# Keypad_Schematic.net
KiCad netlist of a schematic drawn in Altium Designer
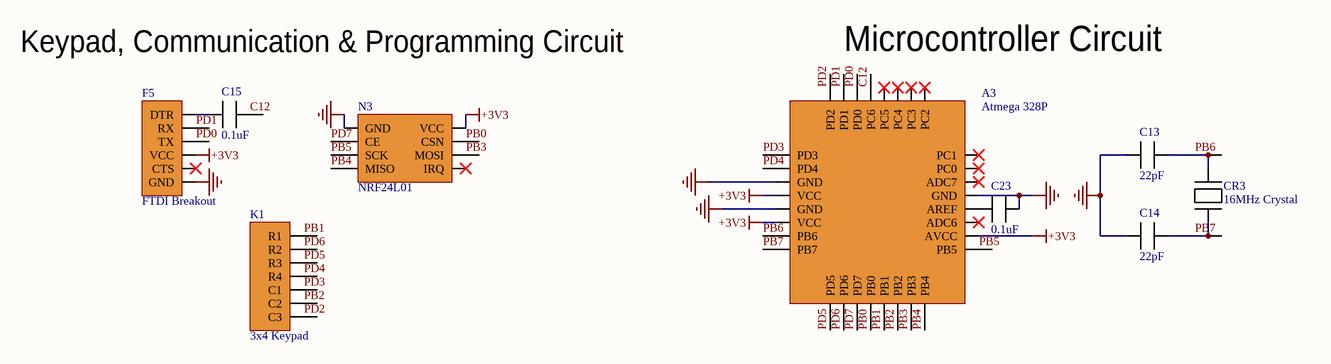
[diagram p0: Keypad Schematic.SchDoc]

(export (version "E")
  (design (tool "Eeschema 10.0.6"))
  (components
    (comp (ref "A3")
      (value "Atmega 328P")
      (footprint "ATMega328P")
      (description "IC MCU 8BIT 32KB FLASH 32TQFP")
      (fields
        (field (name "MANUFACTURER") "Microchip")
        (field (name "MANUFACTURER PART NUMBER") "ATMEGA328PB-AUR")
      )
      (libsource (lib "Schematic Library") (part "ATMEGA328PB-AUR"))
    )
    (comp (ref "C13")
      (value "22pF")
      (footprint "22pF Capacitor")
      (description "Cap Ceramic 22pF 50V C0G 5% SMD 0603 125C Paper T/R")
      (fields
        (field (name "MANUFACTURER") "Kyocera AVX")
        (field (name "MANUFACTURER PART NUMBER") "06035A220JAT2A")
      )
      (libsource (lib "Schematic Library") (part "06035A220JAT2A"))
    )
    (comp (ref "C14")
      (value "22pF")
      (footprint "22pF Capacitor")
      (description "Cap Ceramic 22pF 50V C0G 5% SMD 0603 125C Paper T/R")
      (fields
        (field (name "MANUFACTURER") "Kyocera AVX")
        (field (name "MANUFACTURER PART NUMBER") "06035A220JAT2A")
      )
      (libsource (lib "Schematic Library") (part "06035A220JAT2A"))
    )
    (comp (ref "C15")
      (value "0.1uF")
      (footprint "0.1uF Capacitor")
      (description "CAP CER 0.1UF 25V X7R 0603")
      (fields
        (field (name "MANUFACTURER") "Kyocera AVX")
        (field (name "MANUFACTURER PART NUMBER") "06033C104KAT4A")
      )
      (libsource (lib "Schematic Library") (part "06033C104KAT4A"))
    )
    (comp (ref "C23")
      (value "0.1uF")
      (footprint "0.1uF Capacitor")
      (description "CAP CER 0.1UF 25V X7R 0603")
      (fields
        (field (name "MANUFACTURER") "Kyocera AVX")
        (field (name "MANUFACTURER PART NUMBER") "06033C104KAT4A")
      )
      (libsource (lib "Schematic Library") (part "06033C104KAT4A"))
    )
    (comp (ref "CR3")
      (value "16MHz Crystal")
      (footprint "16MHz Crystal")
      (description "CRYSTAL 16.0000MHZ 20PF SMD")
      (fields
        (field (name "MANUFACTURER") "ECS International")
        (field (name "MANUFACTURER PART NUMBER") "ECS-160-20-3X-TR")
      )
      (libsource (lib "Schematic Library") (part "ECS-160-20-3X-TR"))
    )
    (comp (ref "F5")
      (value "FTDI Breakout")
      (footprint "FTDI")
      (description "FTDI USB to TTL serial converter module")
      (libsource (lib "Schematic Library") (part "FTDI"))
    )
    (comp (ref "K1")
      (value "3x4 Keypad")
      (footprint "3x4 Keypad")
      (description "Membrane 3X4 Matrix Keypad + Extras - 3X4")
      (fields
        (field (name "MANUFACTURER") "Adafruit Industries")
        (field (name "MANUFACTURER PART NUMBER") "419")
      )
      (libsource (lib "Schematic Library") (part "419"))
    )
    (comp (ref "N3")
      (value "NRF24L01")
      (footprint "NRF24L01")
      (description "3.3V NRF24L01 WIRELESS RF MODULE")
      (libsource (lib "Schematic Library") (part "NRF24L01"))
    )
  )
  (nets
    (net (code "1") (name "+3V3") (class "Default")
      (node (ref "A3") (pin "18") (pinfunction "AVCC_18") (pintype "passive"))
      (node (ref "A3") (pin "4") (pinfunction "VCC_4") (pintype "passive"))
      (node (ref "A3") (pin "6") (pinfunction "VCC_6") (pintype "passive"))
      (node (ref "F5") (pin "4") (pinfunction "VCC_4") (pintype "passive"))
      (node (ref "N3") (pin "5") (pinfunction "VCC_5") (pintype "passive"))
    )
    (net (code "2") (name "/C12") (class "Default")
      (node (ref "A3") (pin "29") (pinfunction "PC6_29") (pintype "passive"))
      (node (ref "C15") (pin "2") (pinfunction "2_2") (pintype "passive"))
    )
    (net (code "3") (name "/PB0") (class "Default")
      (node (ref "A3") (pin "12") (pinfunction "PB0_12") (pintype "passive"))
      (node (ref "N3") (pin "6") (pinfunction "CSN_6") (pintype "passive"))
    )
    (net (code "4") (name "/PB1") (class "Default")
      (node (ref "A3") (pin "13") (pinfunction "PB1_13") (pintype "passive"))
      (node (ref "K1") (pin "1") (pinfunction "R1_1") (pintype "passive"))
    )
    (net (code "5") (name "/PB2") (class "Default")
      (node (ref "A3") (pin "14") (pinfunction "PB2_14") (pintype "passive"))
      (node (ref "K1") (pin "6") (pinfunction "C2_6") (pintype "passive"))
    )
    (net (code "6") (name "/PB3") (class "Default")
      (node (ref "A3") (pin "15") (pinfunction "PB3_15") (pintype "passive"))
      (node (ref "N3") (pin "7") (pinfunction "MOSI_7") (pintype "passive"))
    )
    (net (code "7") (name "/PB4") (class "Default")
      (node (ref "A3") (pin "16") (pinfunction "PB4_16") (pintype "passive"))
      (node (ref "N3") (pin "4") (pinfunction "MISO_4") (pintype "passive"))
    )
    (net (code "8") (name "/PB5") (class "Default")
      (node (ref "A3") (pin "17") (pinfunction "PB5_17") (pintype "passive"))
      (node (ref "N3") (pin "3") (pinfunction "SCK_3") (pintype "passive"))
    )
    (net (code "9") (name "/PB6") (class "Default")
      (node (ref "A3") (pin "7") (pinfunction "PB6_7") (pintype "passive"))
      (node (ref "C13") (pin "2") (pinfunction "2_2") (pintype "passive"))
      (node (ref "CR3") (pin "2") (pinfunction "2_2") (pintype "passive"))
    )
    (net (code "10") (name "/PB7") (class "Default")
      (node (ref "A3") (pin "8") (pinfunction "PB7_8") (pintype "passive"))
      (node (ref "C14") (pin "2") (pinfunction "2_2") (pintype "passive"))
      (node (ref "CR3") (pin "1") (pinfunction "1_1") (pintype "passive"))
    )
    (net (code "11") (name "/PD0") (class "Default")
      (node (ref "A3") (pin "30") (pinfunction "PD0_30") (pintype "passive"))
      (node (ref "F5") (pin "3") (pinfunction "TX_3") (pintype "passive"))
    )
    (net (code "12") (name "/PD1") (class "Default")
      (node (ref "A3") (pin "31") (pinfunction "PD1_31") (pintype "passive"))
      (node (ref "F5") (pin "2") (pinfunction "RX_2") (pintype "passive"))
    )
    (net (code "13") (name "/PD2") (class "Default")
      (node (ref "A3") (pin "32") (pinfunction "PD2_32") (pintype "passive"))
      (node (ref "K1") (pin "7") (pinfunction "C3_7") (pintype "passive"))
    )
    (net (code "14") (name "/PD3") (class "Default")
      (node (ref "A3") (pin "1") (pinfunction "PD3_1") (pintype "passive"))
      (node (ref "K1") (pin "5") (pinfunction "C1_5") (pintype "passive"))
    )
    (net (code "15") (name "/PD4") (class "Default")
      (node (ref "A3") (pin "2") (pinfunction "PD4_2") (pintype "passive"))
      (node (ref "K1") (pin "4") (pinfunction "R4_4") (pintype "passive"))
    )
    (net (code "16") (name "/PD5") (class "Default")
      (node (ref "A3") (pin "9") (pinfunction "PD5_9") (pintype "passive"))
      (node (ref "K1") (pin "3") (pinfunction "R3_3") (pintype "passive"))
    )
    (net (code "17") (name "/PD6") (class "Default")
      (node (ref "A3") (pin "10") (pinfunction "PD6_10") (pintype "passive"))
      (node (ref "K1") (pin "2") (pinfunction "R2_2") (pintype "passive"))
    )
    (net (code "18") (name "/PD7") (class "Default")
      (node (ref "A3") (pin "11") (pinfunction "PD7_11") (pintype "passive"))
      (node (ref "N3") (pin "2") (pinfunction "CE_2") (pintype "passive"))
    )
    (net (code "19") (name "GND") (class "Default")
      (node (ref "A3") (pin "21") (pinfunction "GND_21") (pintype "passive"))
      (node (ref "A3") (pin "3") (pinfunction "GND_3") (pintype "passive"))
      (node (ref "A3") (pin "5") (pinfunction "GND_5") (pintype "passive"))
      (node (ref "C13") (pin "1") (pinfunction "1_1") (pintype "passive"))
      (node (ref "C14") (pin "1") (pinfunction "1_1") (pintype "passive"))
      (node (ref "C23") (pin "2") (pinfunction "2_2") (pintype "passive"))
      (node (ref "F5") (pin "6") (pinfunction "GND_6") (pintype "passive"))
      (node (ref "N3") (pin "1") (pinfunction "GND_1") (pintype "passive"))
    )
    (net (code "20") (name "Net-(A3-AREF)") (class "Default")
      (node (ref "A3") (pin "20") (pinfunction "AREF_20") (pintype "passive"))
      (node (ref "C23") (pin "1") (pinfunction "1_1") (pintype "passive"))
    )
    (net (code "21") (name "Net-(F5-DTR)") (class "Default")
      (node (ref "C15") (pin "1") (pinfunction "1_1") (pintype "passive"))
      (node (ref "F5") (pin "1") (pinfunction "DTR_1") (pintype "passive"))
    )
    (net (code "22") (name "unconnected-(A3-ADC6-Pad19)") (class "Default")
      (node (ref "A3") (pin "19") (pinfunction "ADC6_19") (pintype "passive+no_connect"))
    )
    (net (code "23") (name "unconnected-(A3-ADC7-Pad22)") (class "Default")
      (node (ref "A3") (pin "22") (pinfunction "ADC7_22") (pintype "passive+no_connect"))
    )
    (net (code "24") (name "unconnected-(A3-PC0-Pad23)") (class "Default")
      (node (ref "A3") (pin "23") (pinfunction "PC0_23") (pintype "passive+no_connect"))
    )
    (net (code "25") (name "unconnected-(A3-PC1-Pad24)") (class "Default")
      (node (ref "A3") (pin "24") (pinfunction "PC1_24") (pintype "passive+no_connect"))
    )
    (net (code "26") (name "unconnected-(A3-PC2-Pad25)") (class "Default")
      (node (ref "A3") (pin "25") (pinfunction "PC2_25") (pintype "passive+no_connect"))
    )
    (net (code "27") (name "unconnected-(A3-PC3-Pad26)") (class "Default")
      (node (ref "A3") (pin "26") (pinfunction "PC3_26") (pintype "passive+no_connect"))
    )
    (net (code "28") (name "unconnected-(A3-PC4-Pad27)") (class "Default")
      (node (ref "A3") (pin "27") (pinfunction "PC4_27") (pintype "passive+no_connect"))
    )
    (net (code "29") (name "unconnected-(A3-PC5-Pad28)") (class "Default")
      (node (ref "A3") (pin "28") (pinfunction "PC5_28") (pintype "passive+no_connect"))
    )
    (net (code "30") (name "unconnected-(F5-CTS-Pad5)") (class "Default")
      (node (ref "F5") (pin "5") (pinfunction "CTS_5") (pintype "passive+no_connect"))
    )
    (net (code "31") (name "unconnected-(N3-IRQ-Pad8)") (class "Default")
      (node (ref "N3") (pin "8") (pinfunction "IRQ_8") (pintype "passive+no_connect"))
    )
  )
)
